# SGP40_Breakout.net
KiCad netlist of a schematic drawn in EAGLE
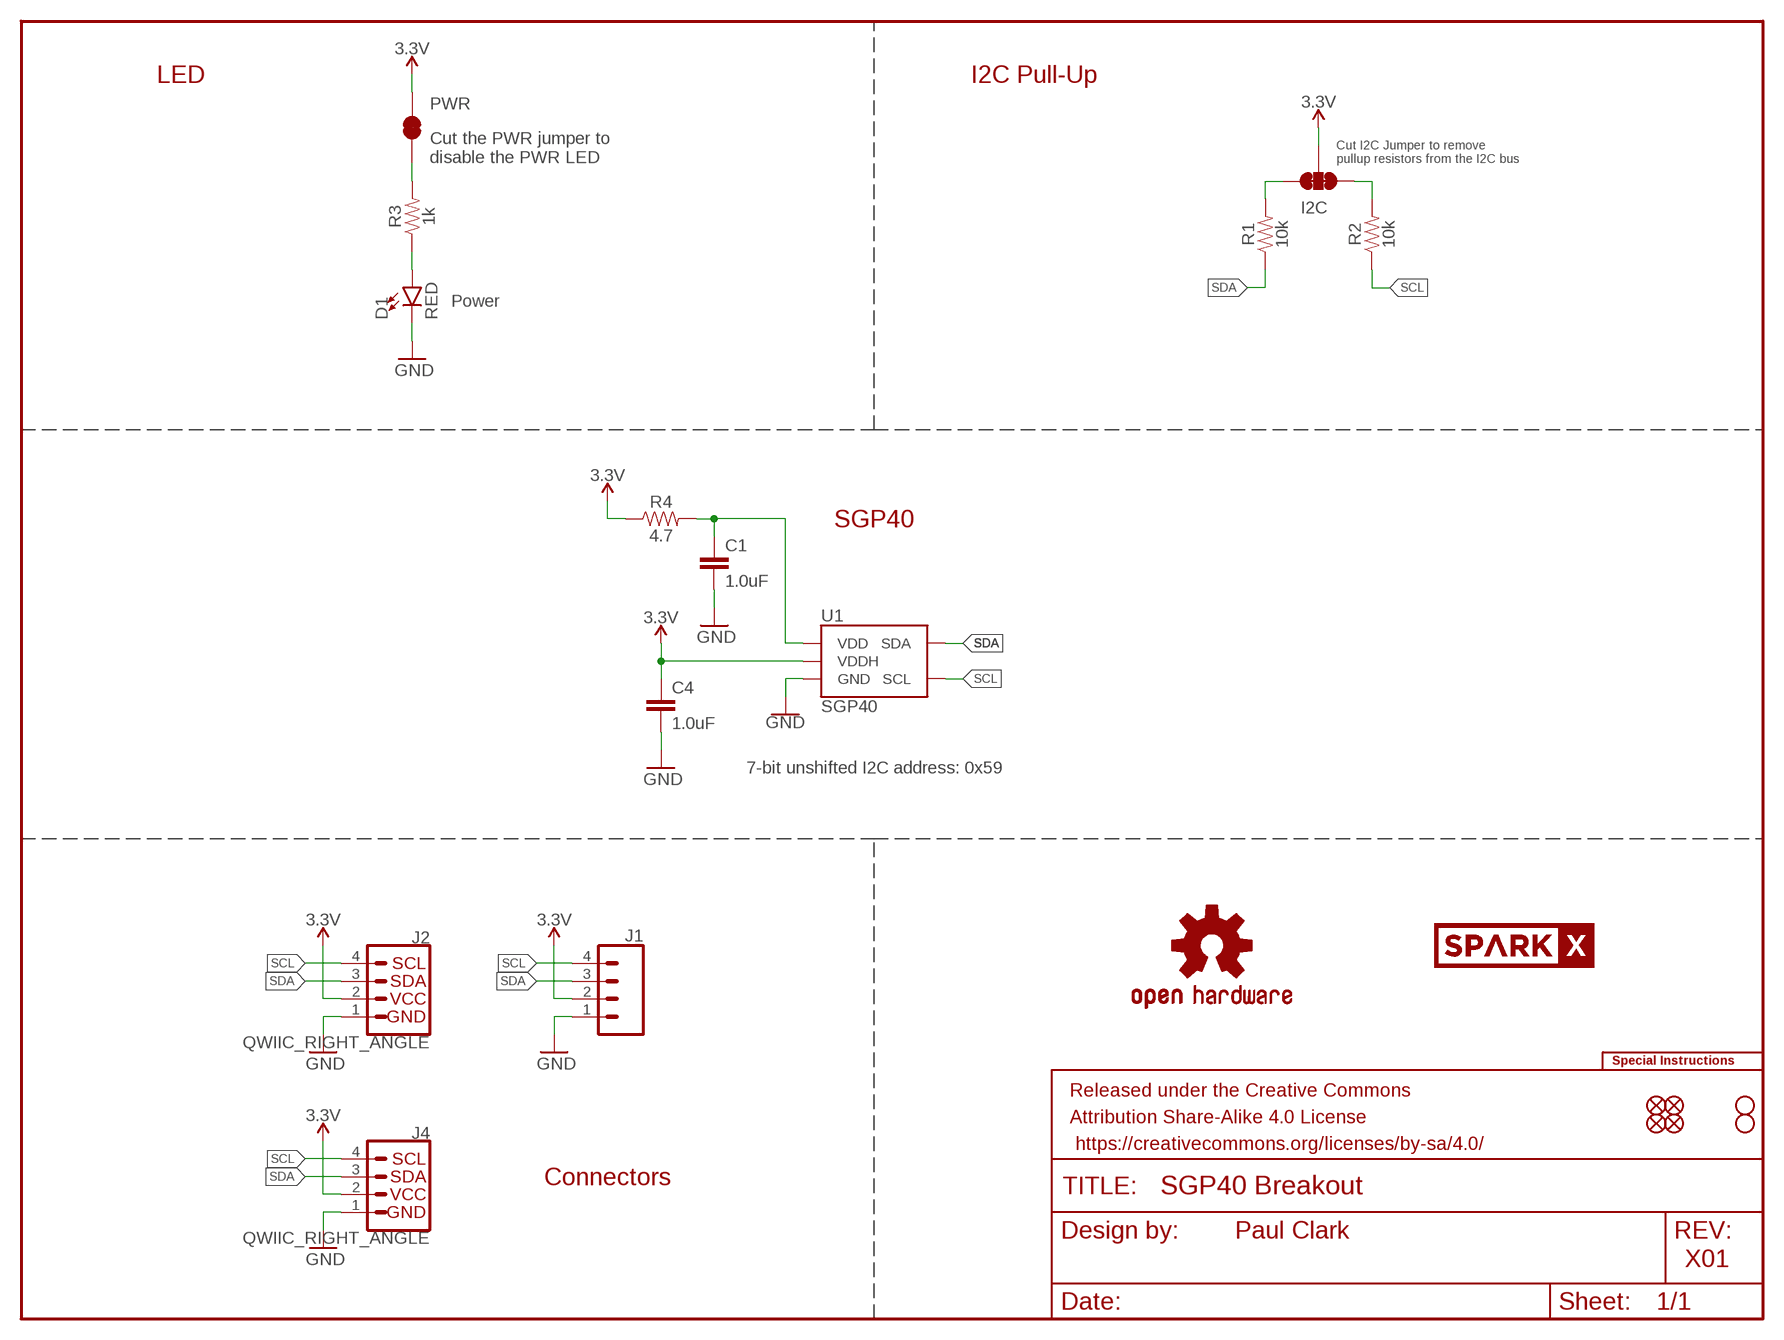
[diagram p0: schematic, sheet 1]

(export (version "E")
  (design (tool "Eeschema 10.0.6"))
  (components
    (comp (ref "C1")
      (value "1.0uF")
      (footprint "eagle-import:0603")
      (libsource (lib "eagle-import") (part "1.0UF-0603-16V-10%-X7R"))
    )
    (comp (ref "C4")
      (value "1.0uF")
      (footprint "eagle-import:0603")
      (libsource (lib "eagle-import") (part "1.0UF-0603-16V-10%-X7R"))
    )
    (comp (ref "D1")
      (value "RED")
      (footprint "eagle-import:LED-0603")
      (libsource (lib "eagle-import") (part "LED-RED0603"))
    )
    (comp (ref "FRAME1")
      (value "FRAME-LETTER")
      (footprint "eagle-import:CREATIVE_COMMONS")
      (libsource (lib "eagle-import") (part "FRAME-LETTER"))
    )
    (comp (ref "I2C")
      (value "JUMPER-SMT_3_2-NC_TRACE_SILK")
      (footprint "eagle-import:SMT-JUMPER_3_2-NC_TRACE_SILK")
      (libsource (lib "eagle-import") (part "JUMPER-SMT_3_2-NC_TRACE_SILK"))
    )
    (comp (ref "J1")
      (value "CONN_041X04_NO_SILK")
      (footprint "eagle-import:1X04_NO_SILK")
      (libsource (lib "eagle-import") (part "CONN_041X04_NO_SILK"))
    )
    (comp (ref "J2")
      (value "QWIIC_RIGHT_ANGLE")
      (footprint "eagle-import:JST04_1MM_RA")
      (libsource (lib "eagle-import") (part "QWIIC_CONNECTORJS-1MM"))
    )
    (comp (ref "J4")
      (value "QWIIC_RIGHT_ANGLE")
      (footprint "eagle-import:JST04_1MM_RA")
      (libsource (lib "eagle-import") (part "QWIIC_CONNECTORJS-1MM"))
    )
    (comp (ref "JP1")
      (value "FIDUCIAL1X2")
      (footprint "eagle-import:FIDUCIAL-1X2")
      (libsource (lib "eagle-import") (part "FIDUCIAL1X2"))
    )
    (comp (ref "JP2")
      (value "FIDUCIAL1X2")
      (footprint "eagle-import:FIDUCIAL-1X2")
      (libsource (lib "eagle-import") (part "FIDUCIAL1X2"))
    )
    (comp (ref "JP3")
      (value "STAND-OFF")
      (footprint "eagle-import:STAND-OFF")
      (libsource (lib "eagle-import") (part "STAND-OFF"))
    )
    (comp (ref "JP4")
      (value "STAND-OFF")
      (footprint "eagle-import:STAND-OFF")
      (libsource (lib "eagle-import") (part "STAND-OFF"))
    )
    (comp (ref "JP5")
      (value "FIDUCIAL1X2")
      (footprint "eagle-import:FIDUCIAL-1X2")
      (libsource (lib "eagle-import") (part "FIDUCIAL1X2"))
    )
    (comp (ref "JP6")
      (value "FIDUCIAL1X2")
      (footprint "eagle-import:FIDUCIAL-1X2")
      (libsource (lib "eagle-import") (part "FIDUCIAL1X2"))
    )
    (comp (ref "LOGO1")
      (value "SPECIAL_INSTRUCTIONS-ORDERING")
      (footprint "eagle-import:ORDERING_INSTRUCTIONS")
      (libsource (lib "eagle-import") (part "SPECIAL_INSTRUCTIONS-ORDERING"))
    )
    (comp (ref "LOGO5")
      (value "OSHW-LOGOS")
      (footprint "eagle-import:OSHW-LOGO-S")
      (libsource (lib "eagle-import") (part "OSHW-LOGOS"))
    )
    (comp (ref "PWR")
      (value "JUMPER-SMT_2_NC_TRACE_SILK")
      (footprint "eagle-import:SMT-JUMPER_2_NC_TRACE_SILK")
      (libsource (lib "eagle-import") (part "JUMPER-SMT_2_NC_TRACE_SILK"))
    )
    (comp (ref "R1")
      (value "10k")
      (footprint "eagle-import:0603")
      (libsource (lib "eagle-import") (part "10KOHM-0603-1/10W-1%"))
    )
    (comp (ref "R2")
      (value "10k")
      (footprint "eagle-import:0603")
      (libsource (lib "eagle-import") (part "10KOHM-0603-1/10W-1%"))
    )
    (comp (ref "R3")
      (value "1k")
      (footprint "eagle-import:0603")
      (libsource (lib "eagle-import") (part "1KOHM-0603-1/10W-1%"))
    )
    (comp (ref "R4")
      (value "4.7")
      (footprint "eagle-import:0603")
      (libsource (lib "eagle-import") (part "4.7OHM-0603-1/10W-1%"))
    )
    (comp (ref "U$10")
      (value "SPARKX-LOGO3")
      (footprint "eagle-import:SPARKX-SMALL")
      (libsource (lib "eagle-import") (part "SPARKX-LOGO3"))
    )
    (comp (ref "U$18")
      (value "SPARKX-LOGO3")
      (footprint "eagle-import:SPARKX-SMALL")
      (libsource (lib "eagle-import") (part "SPARKX-LOGO3"))
    )
    (comp (ref "U1")
      (value "SGP40")
      (footprint "eagle-import:SGP40")
      (fields (field (name "DIGIKEY_PART") "1649-SGP40-D-R4CT-ND"))
      (libsource (lib "eagle-import") (part "SGP40"))
    )
  )
  (nets
    (net (code "1") (name "3.3V") (class "Default")
      (node (ref "C4") (pin "1") (pinfunction "1_1") (pintype "passive"))
      (node (ref "I2C") (pin "2") (pinfunction "2_2") (pintype "passive"))
      (node (ref "J1") (pin "2") (pinfunction "2_2") (pintype "passive"))
      (node (ref "J2") (pin "2") (pinfunction "2_2") (pintype "power_in"))
      (node (ref "J4") (pin "2") (pinfunction "2_2") (pintype "power_in"))
      (node (ref "PWR") (pin "2") (pinfunction "2_2") (pintype "passive"))
      (node (ref "R4") (pin "1") (pinfunction "1_1") (pintype "passive"))
      (node (ref "U1") (pin "5") (pinfunction "VDDH_5") (pintype "power_in"))
    )
    (net (code "2") (name "GND") (class "Default")
      (node (ref "C1") (pin "2") (pinfunction "2_2") (pintype "passive"))
      (node (ref "C4") (pin "2") (pinfunction "2_2") (pintype "passive"))
      (node (ref "D1") (pin "C") (pinfunction "C_C") (pintype "passive"))
      (node (ref "J1") (pin "1") (pinfunction "1_1") (pintype "passive"))
      (node (ref "J2") (pin "1") (pinfunction "1_1") (pintype "power_in"))
      (node (ref "J4") (pin "1") (pinfunction "1_1") (pintype "power_in"))
      (node (ref "U1") (pin "2") (pinfunction "GND_2") (pintype "power_in"))
      (node (ref "U1") (pin "4") (pinfunction "GND_4") (pintype "power_in"))
      (node (ref "U1") (pin "DIEPAD") (pinfunction "GND_DIEPAD") (pintype "power_in"))
    )
    (net (code "3") (name "Net-(D1-PadA)") (class "Default")
      (node (ref "D1") (pin "A") (pinfunction "A_A") (pintype "passive"))
      (node (ref "R3") (pin "1") (pinfunction "1_1") (pintype "passive"))
    )
    (net (code "4") (name "Net-(I2C-Pad1)") (class "Default")
      (node (ref "I2C") (pin "1") (pinfunction "1_1") (pintype "passive"))
      (node (ref "R2") (pin "2") (pinfunction "2_2") (pintype "passive"))
    )
    (net (code "5") (name "Net-(I2C-Pad3)") (class "Default")
      (node (ref "I2C") (pin "3") (pinfunction "3_3") (pintype "passive"))
      (node (ref "R1") (pin "2") (pinfunction "2_2") (pintype "passive"))
    )
    (net (code "6") (name "Net-(PWR-Pad1)") (class "Default")
      (node (ref "PWR") (pin "1") (pinfunction "1_1") (pintype "passive"))
      (node (ref "R3") (pin "2") (pinfunction "2_2") (pintype "passive"))
    )
    (net (code "7") (name "Net-(U1-VDD)") (class "Default")
      (node (ref "C1") (pin "1") (pinfunction "1_1") (pintype "passive"))
      (node (ref "R4") (pin "2") (pinfunction "2_2") (pintype "passive"))
      (node (ref "U1") (pin "1") (pinfunction "VDD_1") (pintype "power_in"))
    )
    (net (code "8") (name "SCL") (class "Default")
      (node (ref "J1") (pin "4") (pinfunction "4_4") (pintype "passive"))
      (node (ref "J2") (pin "4") (pinfunction "4_4") (pintype "passive"))
      (node (ref "J4") (pin "4") (pinfunction "4_4") (pintype "passive"))
      (node (ref "R2") (pin "1") (pinfunction "1_1") (pintype "passive"))
      (node (ref "U1") (pin "6") (pinfunction "SCL_6") (pintype "bidirectional"))
    )
    (net (code "9") (name "SDA") (class "Default")
      (node (ref "J1") (pin "3") (pinfunction "3_3") (pintype "passive"))
      (node (ref "J2") (pin "3") (pinfunction "3_3") (pintype "passive"))
      (node (ref "J4") (pin "3") (pinfunction "3_3") (pintype "passive"))
      (node (ref "R1") (pin "1") (pinfunction "1_1") (pintype "passive"))
      (node (ref "U1") (pin "3") (pinfunction "SDA_3") (pintype "bidirectional"))
    )
  )
)
